# p2c-002-dx.net
KiCad netlist of a schematic drawn in EAGLE
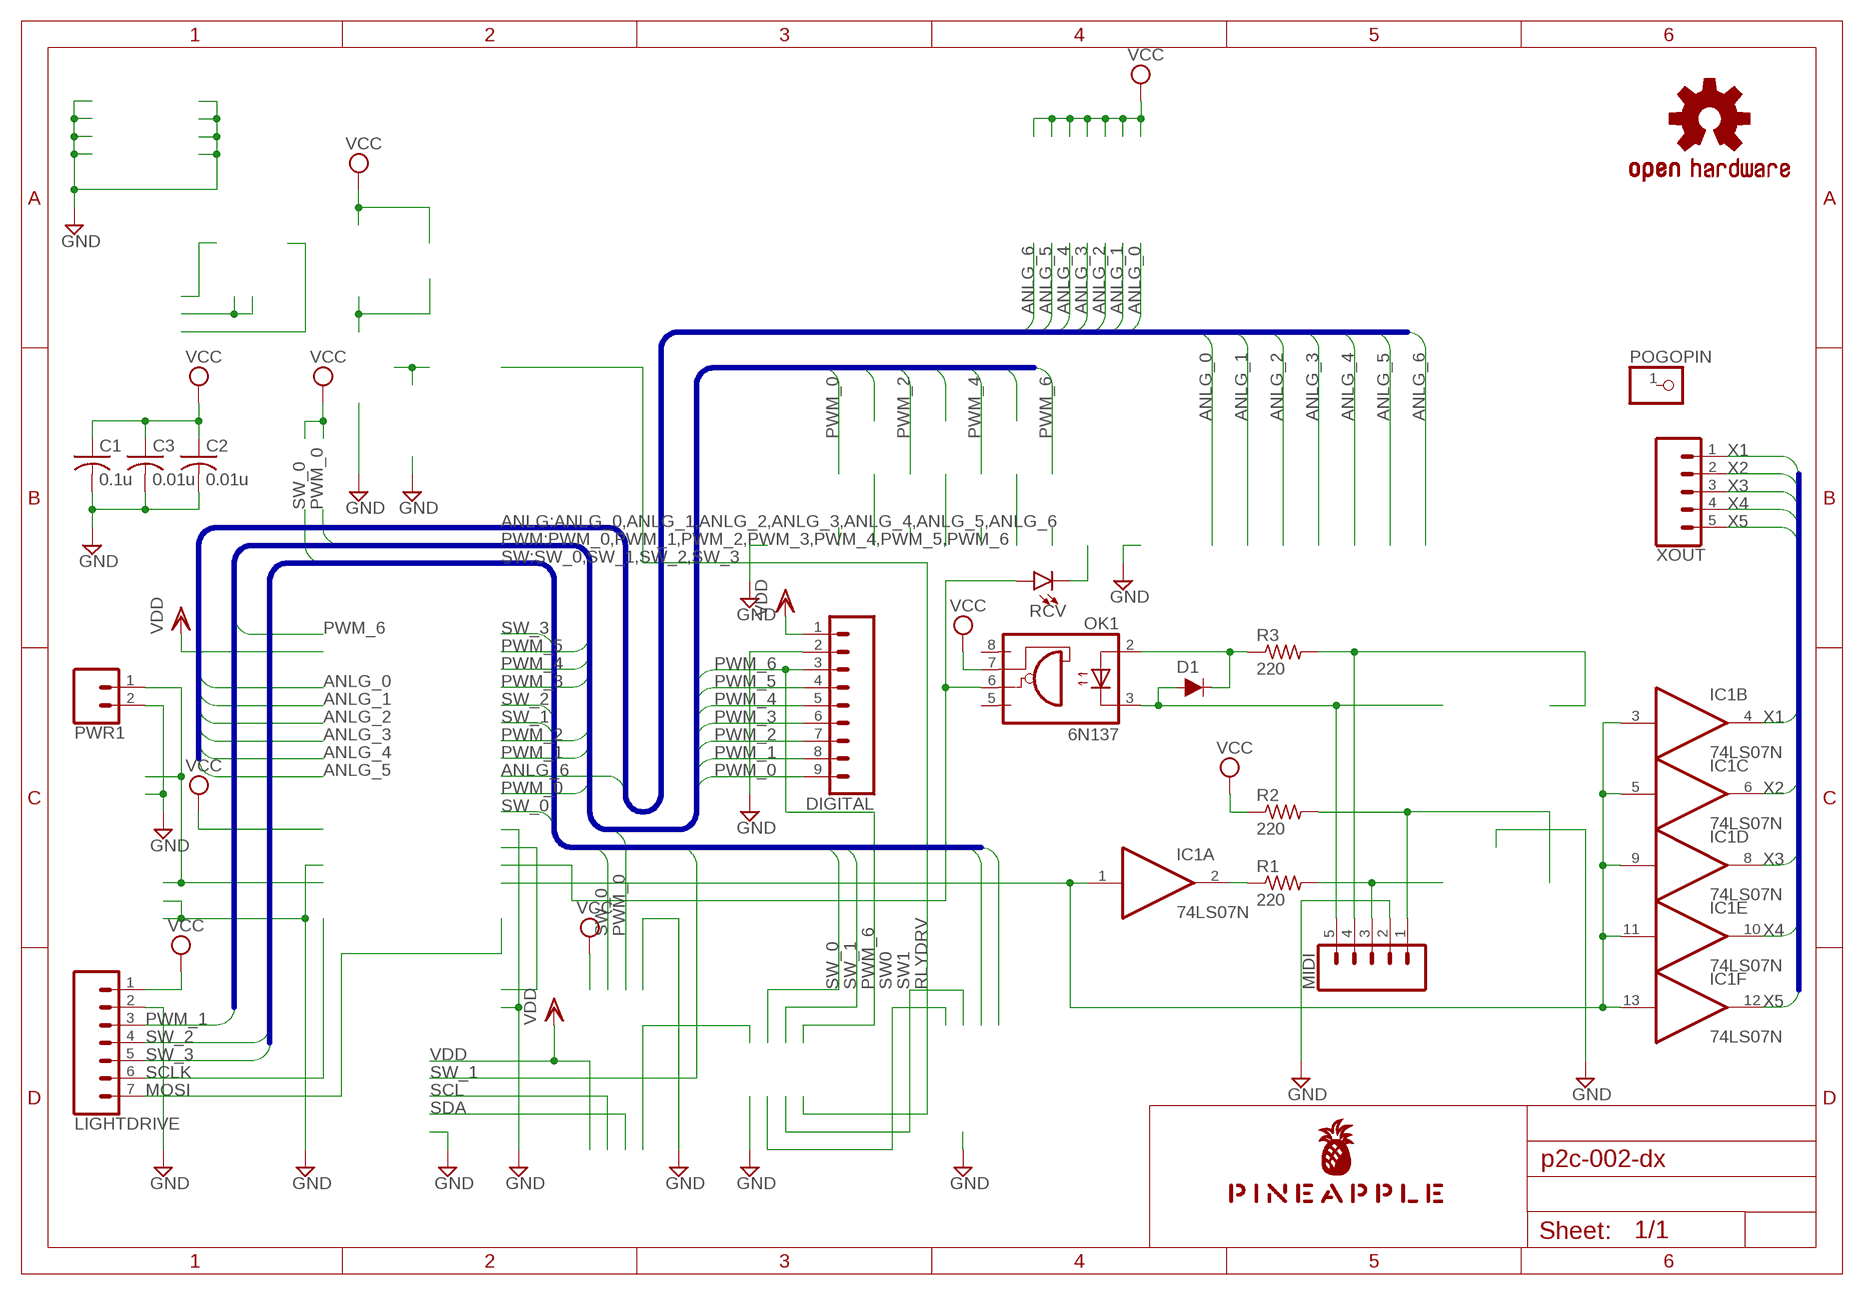
[diagram p0: schematic, sheet 1]

(export (version "E")
  (design (tool "Eeschema 10.0.6"))
  (components
    (comp (ref "C1")
      (value "0.1u")
      (footprint "eagle-import:C025-025X050")
      (libsource (lib "eagle-import") (part "C-US025-025X050"))
    )
    (comp (ref "C2")
      (value "0.01u")
      (footprint "eagle-import:C025-024X044")
      (libsource (lib "eagle-import") (part "C-US025-024X044"))
    )
    (comp (ref "C3")
      (value "0.01u")
      (footprint "eagle-import:C025-024X044")
      (libsource (lib "eagle-import") (part "C-US025-024X044"))
    )
    (comp (ref "D1")
      (value "DIODE-1N4148")
      (footprint "eagle-import:DIODE-1N4148")
      (libsource (lib "eagle-import") (part "DIODE-1N4148"))
    )
    (comp (ref "DIGITAL")
      (value "CONN_09")
      (footprint "eagle-import:1X09")
      (libsource (lib "eagle-import") (part "CONN_09"))
    )
    (comp (ref "IC1")
      (value "74LS07N")
      (footprint "eagle-import:DIL14")
      (libsource (lib "eagle-import") (part "7407NLS"))
    )
    (comp (ref "LIGHTDRIVE")
      (value "CONN_07")
      (footprint "eagle-import:1X07")
      (libsource (lib "eagle-import") (part "CONN_07"))
    )
    (comp (ref "LOGO1")
      (value "OSHW-LOGOS-COPPER")
      (footprint "eagle-import:OSHW-LOGO-S_COPPER")
      (libsource (lib "eagle-import") (part "OSHW-LOGOS-COPPER"))
    )
    (comp (ref "MIDI")
      (value "CONN_05JST")
      (footprint "eagle-import:JST-5-PTH")
      (libsource (lib "eagle-import") (part "CONN_05JST"))
    )
    (comp (ref "OK1")
      (value "6N137")
      (footprint "eagle-import:DIL08")
      (libsource (lib "eagle-import") (part "6N137"))
    )
    (comp (ref "POGOPIN")
      (value "PINHD-1X1")
      (footprint "eagle-import:1X01")
      (libsource (lib "eagle-import") (part "PINHD-1X1"))
    )
    (comp (ref "PWR1")
      (value "CONN_02")
      (footprint "eagle-import:1X02")
      (libsource (lib "eagle-import") (part "CONN_02"))
    )
    (comp (ref "R1")
      (value "220")
      (footprint "eagle-import:0204_5")
      (libsource (lib "eagle-import") (part "R-US_0204/5"))
    )
    (comp (ref "R2")
      (value "220")
      (footprint "eagle-import:0204_5")
      (libsource (lib "eagle-import") (part "R-US_0204/5"))
    )
    (comp (ref "R3")
      (value "220")
      (footprint "eagle-import:0204_5")
      (libsource (lib "eagle-import") (part "R-US_0204/5"))
    )
    (comp (ref "RCV")
      (value "LED-3MM-NO_SILK")
      (footprint "eagle-import:LED_3MM-NS")
      (libsource (lib "eagle-import") (part "LED-3MM-NO_SILK"))
    )
    (comp (ref "U$1")
      (value "PINEAPPLE450_SILK")
      (footprint "eagle-import:PINEAPPLE450_SILK")
      (libsource (lib "eagle-import") (part "PINEAPPLE450_SILK"))
    )
    (comp (ref "XOUT")
      (value "CONN_05")
      (footprint "eagle-import:1X05")
      (libsource (lib "eagle-import") (part "CONN_05"))
    )
  )
  (nets
    (net (code "10") (name "/MOSI") (class "Default")
      (node (ref "LIGHTDRIVE") (pin "7") (pinfunction "7_7") (pintype "passive"))
    )
    (net (code "11") (name "/PWM_0") (class "Default")
      (node (ref "DIGITAL") (pin "9") (pinfunction "9_9") (pintype "passive"))
    )
    (net (code "12") (name "/PWM_1") (class "Default")
      (node (ref "DIGITAL") (pin "8") (pinfunction "8_8") (pintype "passive"))
      (node (ref "LIGHTDRIVE") (pin "3") (pinfunction "3_3") (pintype "passive"))
    )
    (net (code "13") (name "/PWM_2") (class "Default")
      (node (ref "DIGITAL") (pin "7") (pinfunction "7_7") (pintype "passive"))
    )
    (net (code "14") (name "/PWM_3") (class "Default")
      (node (ref "DIGITAL") (pin "6") (pinfunction "6_6") (pintype "passive"))
    )
    (net (code "15") (name "/PWM_4") (class "Default")
      (node (ref "DIGITAL") (pin "5") (pinfunction "5_5") (pintype "passive"))
    )
    (net (code "16") (name "/PWM_5") (class "Default")
      (node (ref "DIGITAL") (pin "4") (pinfunction "4_4") (pintype "passive"))
    )
    (net (code "17") (name "/PWM_6") (class "Default")
      (node (ref "DIGITAL") (pin "3") (pinfunction "3_3") (pintype "passive"))
    )
    (net (code "20") (name "/SCLK") (class "Default")
      (node (ref "LIGHTDRIVE") (pin "6") (pinfunction "6_6") (pintype "passive"))
    )
    (net (code "26") (name "/SW_2") (class "Default")
      (node (ref "LIGHTDRIVE") (pin "4") (pinfunction "4_4") (pintype "passive"))
    )
    (net (code "27") (name "/SW_3") (class "Default")
      (node (ref "LIGHTDRIVE") (pin "5") (pinfunction "5_5") (pintype "passive"))
    )
    (net (code "28") (name "/X1") (class "Default")
      (node (ref "IC1") (pin "4") (pinfunction "O_4") (pintype "open_collector"))
      (node (ref "XOUT") (pin "1") (pinfunction "1_1") (pintype "passive"))
    )
    (net (code "29") (name "/X2") (class "Default")
      (node (ref "IC1") (pin "6") (pinfunction "O_6") (pintype "open_collector"))
      (node (ref "XOUT") (pin "2") (pinfunction "2_2") (pintype "passive"))
    )
    (net (code "30") (name "/X3") (class "Default")
      (node (ref "IC1") (pin "8") (pinfunction "O_8") (pintype "open_collector"))
      (node (ref "XOUT") (pin "3") (pinfunction "3_3") (pintype "passive"))
    )
    (net (code "31") (name "/X4") (class "Default")
      (node (ref "IC1") (pin "10") (pinfunction "O_10") (pintype "open_collector"))
      (node (ref "XOUT") (pin "4") (pinfunction "4_4") (pintype "passive"))
    )
    (net (code "32") (name "/X5") (class "Default")
      (node (ref "IC1") (pin "12") (pinfunction "O_12") (pintype "open_collector"))
      (node (ref "XOUT") (pin "5") (pinfunction "5_5") (pintype "passive"))
    )
    (net (code "35") (name "GND") (class "Default")
      (node (ref "C1") (pin "2") (pinfunction "2_2") (pintype "passive"))
      (node (ref "C2") (pin "2") (pinfunction "2_2") (pintype "passive"))
      (node (ref "C3") (pin "2") (pinfunction "2_2") (pintype "passive"))
      (node (ref "DIGITAL") (pin "2") (pinfunction "2_2") (pintype "passive"))
      (node (ref "LIGHTDRIVE") (pin "2") (pinfunction "2_2") (pintype "passive"))
      (node (ref "MIDI") (pin "2") (pinfunction "2_2") (pintype "passive"))
      (node (ref "PWR1") (pin "2") (pinfunction "2_2") (pintype "passive"))
    )
    (net (code "36") (name "Net-(IC1A-I)") (class "Default")
      (node (ref "IC1") (pin "1") (pinfunction "I_1") (pintype "input"))
      (node (ref "IC1") (pin "11") (pinfunction "I_11") (pintype "input"))
      (node (ref "IC1") (pin "13") (pinfunction "I_13") (pintype "input"))
      (node (ref "IC1") (pin "3") (pinfunction "I_3") (pintype "input"))
      (node (ref "IC1") (pin "5") (pinfunction "I_5") (pintype "input"))
      (node (ref "IC1") (pin "9") (pinfunction "I_9") (pintype "input"))
    )
    (net (code "37") (name "Net-(IC1A-O)") (class "Default")
      (node (ref "IC1") (pin "2") (pinfunction "O_2") (pintype "open_collector"))
      (node (ref "R1") (pin "1") (pinfunction "1_1") (pintype "passive"))
    )
    (net (code "38") (name "Net-(MIDI-Pad1)") (class "Default")
      (node (ref "MIDI") (pin "1") (pinfunction "1_1") (pintype "passive"))
      (node (ref "R2") (pin "2") (pinfunction "2_2") (pintype "passive"))
    )
    (net (code "39") (name "Net-(MIDI-Pad3)") (class "Default")
      (node (ref "MIDI") (pin "3") (pinfunction "3_3") (pintype "passive"))
      (node (ref "R1") (pin "2") (pinfunction "2_2") (pintype "passive"))
    )
    (net (code "40") (name "Net-(MIDI-Pad4)") (class "Default")
      (node (ref "MIDI") (pin "4") (pinfunction "4_4") (pintype "passive"))
      (node (ref "R3") (pin "2") (pinfunction "2_2") (pintype "passive"))
    )
    (net (code "41") (name "Net-(OK1-A)") (class "Default")
      (node (ref "D1") (pin "C") (pinfunction "C_C") (pintype "passive"))
      (node (ref "OK1") (pin "2") (pinfunction "A_2") (pintype "passive"))
      (node (ref "R3") (pin "1") (pinfunction "1_1") (pintype "passive"))
    )
    (net (code "42") (name "Net-(OK1-C)") (class "Default")
      (node (ref "D1") (pin "A") (pinfunction "A_A") (pintype "passive"))
      (node (ref "MIDI") (pin "5") (pinfunction "5_5") (pintype "passive"))
      (node (ref "OK1") (pin "3") (pinfunction "C_3") (pintype "passive"))
    )
    (net (code "43") (name "Net-(OK1-VO)") (class "Default")
      (node (ref "OK1") (pin "6") (pinfunction "VO_6") (pintype "passive"))
      (node (ref "RCV") (pin "A") (pinfunction "A_A") (pintype "passive"))
    )
    (net (code "44") (name "VCC") (class "Default")
      (node (ref "C1") (pin "1") (pinfunction "1_1") (pintype "passive"))
      (node (ref "C2") (pin "1") (pinfunction "1_1") (pintype "passive"))
      (node (ref "C3") (pin "1") (pinfunction "1_1") (pintype "passive"))
      (node (ref "LIGHTDRIVE") (pin "1") (pinfunction "1_1") (pintype "passive"))
      (node (ref "OK1") (pin "7") (pinfunction "VE_7") (pintype "passive"))
      (node (ref "R2") (pin "1") (pinfunction "1_1") (pintype "passive"))
    )
    (net (code "45") (name "VDD") (class "Default")
      (node (ref "DIGITAL") (pin "1") (pinfunction "1_1") (pintype "passive"))
    )
    (net (code "46") (name "unconnected-(OK1-GND-Pad5)") (class "Default")
      (node (ref "OK1") (pin "5") (pinfunction "GND_5") (pintype "passive"))
    )
    (net (code "47") (name "unconnected-(OK1-VCC-Pad8)") (class "Default")
      (node (ref "OK1") (pin "8") (pinfunction "VCC_8") (pintype "passive"))
    )
    (net (code "48") (name "unconnected-(POGOPIN-Pad1)") (class "Default")
      (node (ref "POGOPIN") (pin "1") (pinfunction "1_1") (pintype "passive"))
    )
    (net (code "49") (name "unconnected-(PWR1-Pad1)") (class "Default")
      (node (ref "PWR1") (pin "1") (pinfunction "1_1") (pintype "passive"))
    )
    (net (code "50") (name "unconnected-(RCV-C-PadK)") (class "Default")
      (node (ref "RCV") (pin "K") (pinfunction "C_K") (pintype "passive"))
    )
  )
)
